# pic18f46k22_evb.net
KiCad netlist of a schematic drawn in EAGLE
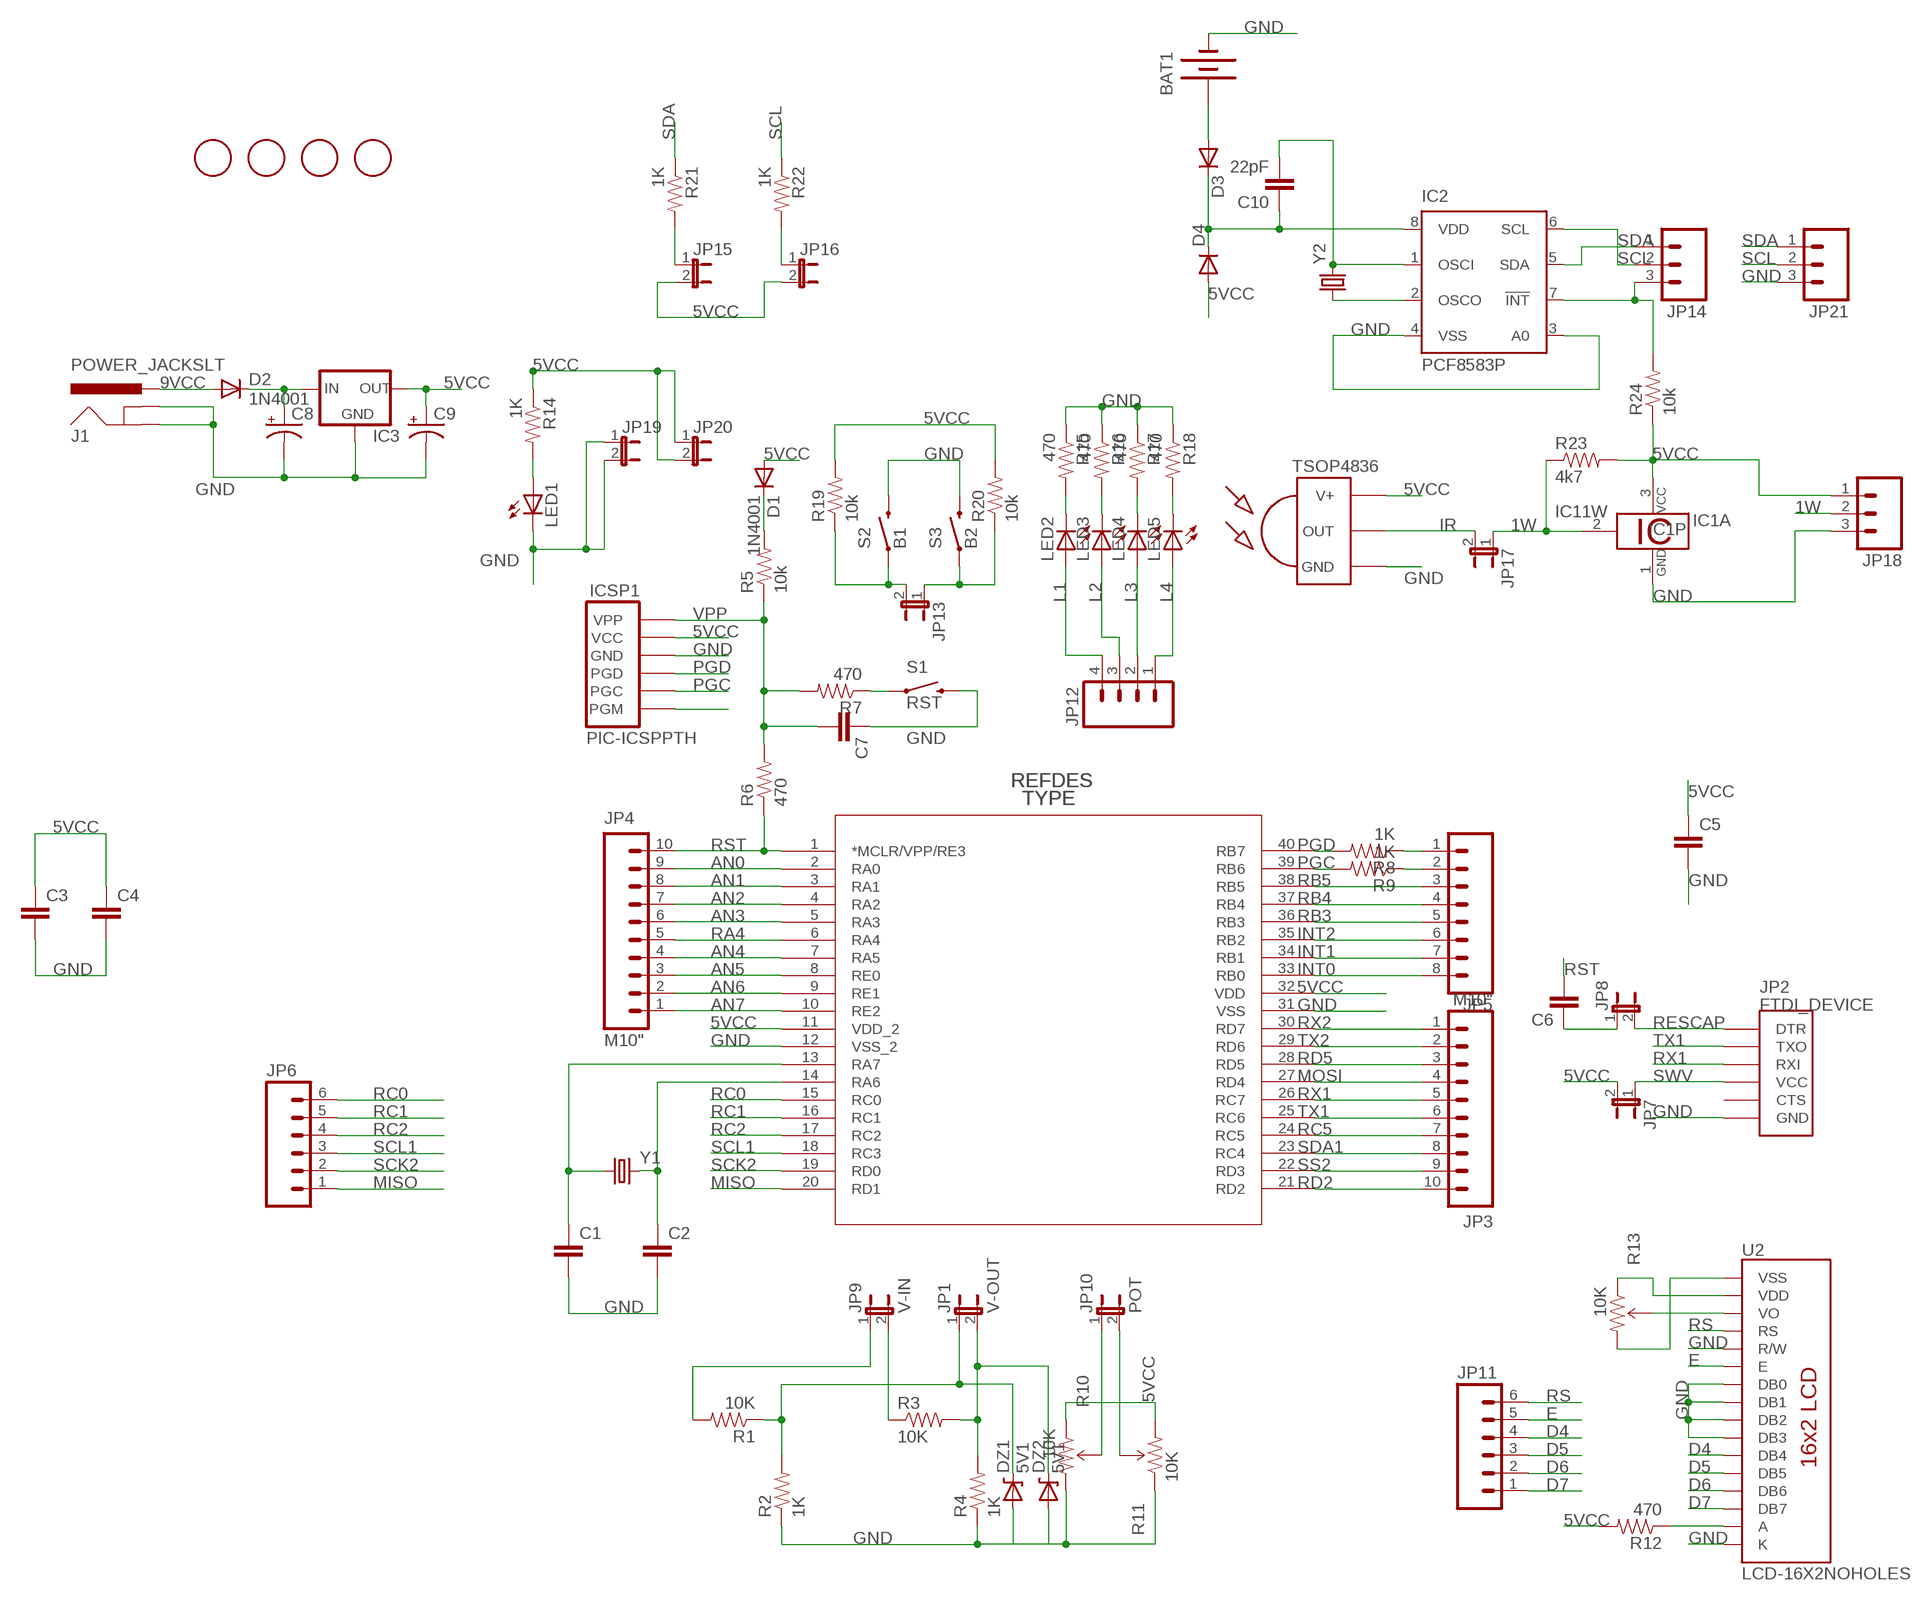
[diagram p0: schematic, sheet 1]

(export (version "E")
  (design (tool "Eeschema 10.0.6"))
  (components
    (comp (ref "BAT1")
      (value "BATTERY12MM")
      (footprint "eagle-import:BATTCON_12MM")
      (libsource (lib "eagle-import") (part "BATTERY12MM"))
    )
    (comp (ref "C1")
      (value "CAPPTH1")
      (footprint "eagle-import:CAP-PTH-5MM")
      (libsource (lib "eagle-import") (part "CAPPTH1"))
    )
    (comp (ref "C2")
      (value "CAPPTH1")
      (footprint "eagle-import:CAP-PTH-5MM")
      (libsource (lib "eagle-import") (part "CAPPTH1"))
    )
    (comp (ref "C3")
      (value "CAPPTH1")
      (footprint "eagle-import:CAP-PTH-5MM")
      (libsource (lib "eagle-import") (part "CAPPTH1"))
    )
    (comp (ref "C4")
      (value "CAPPTH1")
      (footprint "eagle-import:CAP-PTH-5MM")
      (libsource (lib "eagle-import") (part "CAPPTH1"))
    )
    (comp (ref "C5")
      (value "CAPPTH1")
      (footprint "eagle-import:CAP-PTH-5MM")
      (libsource (lib "eagle-import") (part "CAPPTH1"))
    )
    (comp (ref "C6")
      (value "CAPPTH1")
      (footprint "eagle-import:CAP-PTH-5MM")
      (libsource (lib "eagle-import") (part "CAPPTH1"))
    )
    (comp (ref "C7")
      (value "CAPPTH1")
      (footprint "eagle-import:CAP-PTH-5MM")
      (libsource (lib "eagle-import") (part "CAPPTH1"))
    )
    (comp (ref "C8")
      (value "CAP_POLPTH1")
      (footprint "eagle-import:CPOL-RADIAL-100UF-25V")
      (libsource (lib "eagle-import") (part "CAP_POLPTH1"))
    )
    (comp (ref "C9")
      (value "CAP_POLPTH2")
      (footprint "eagle-import:CPOL-RADIAL-10UF-25V")
      (libsource (lib "eagle-import") (part "CAP_POLPTH2"))
    )
    (comp (ref "C10")
      (value "22pF")
      (footprint "eagle-import:CAP-PTH-5MM")
      (libsource (lib "eagle-import") (part "CAPPTH1"))
    )
    (comp (ref "D1")
      (value "1N4001")
      (footprint "eagle-import:DIODE-1N4001")
      (libsource (lib "eagle-import") (part "DIODEPTH"))
    )
    (comp (ref "D2")
      (value "1N4001")
      (footprint "eagle-import:DIODE-1N4001")
      (libsource (lib "eagle-import") (part "DIODEPTH"))
    )
    (comp (ref "D3")
      (value "DIODE1N4148")
      (footprint "eagle-import:DIODE-1N4148")
      (libsource (lib "eagle-import") (part "DIODE1N4148"))
    )
    (comp (ref "D4")
      (value "DIODE1N4148")
      (footprint "eagle-import:DIODE-1N4148")
      (libsource (lib "eagle-import") (part "DIODE1N4148"))
    )
    (comp (ref "DZ1")
      (value "5V1")
      (footprint "eagle-import:DIODE-ZENER")
      (libsource (lib "eagle-import") (part "DIODE-ZENERPTH"))
    )
    (comp (ref "DZ2")
      (value "5V1")
      (footprint "eagle-import:DIODE-ZENER")
      (libsource (lib "eagle-import") (part "DIODE-ZENERPTH"))
    )
    (comp (ref "IC1")
      (value "DS18B20")
      (footprint "eagle-import:TO92-")
      (libsource (lib "eagle-import") (part "DS18B20"))
    )
    (comp (ref "IC2")
      (value "PCF8583P")
      (footprint "eagle-import:DIL08")
      (libsource (lib "eagle-import") (part "PCF8583P"))
    )
    (comp (ref "IC3")
      (value "V_REG_78XXSINK")
      (footprint "eagle-import:TO220-IGO")
      (libsource (lib "eagle-import") (part "V_REG_78XXSINK"))
    )
    (comp (ref "ICSP1")
      (value "PIC-ICSPPTH")
      (footprint "eagle-import:MOLEX-1X6")
      (libsource (lib "eagle-import") (part "PIC-ICSPPTH"))
    )
    (comp (ref "J1")
      (value "POWER_JACKSLT")
      (footprint "eagle-import:POWER_JACK_SLOT")
      (libsource (lib "eagle-import") (part "POWER_JACKSLT"))
    )
    (comp (ref "JP1")
      (value "V-OUT")
      (footprint "eagle-import:1X02")
      (libsource (lib "eagle-import") (part "JUMPER-2PTH"))
    )
    (comp (ref "JP2")
      (value "FTDI_DEVICE")
      (footprint "eagle-import:FTDI_DEVICE_SIDE")
      (libsource (lib "eagle-import") (part "FTDI_DEVICE"))
    )
    (comp (ref "JP3")
      (value "M10\"")
      (footprint "eagle-import:1X10")
      (libsource (lib "eagle-import") (part "M10{dblquote}"))
    )
    (comp (ref "JP4")
      (value "M10\"")
      (footprint "eagle-import:1X10")
      (libsource (lib "eagle-import") (part "M10{dblquote}"))
    )
    (comp (ref "JP5")
      (value "M081X08")
      (footprint "eagle-import:1X08")
      (libsource (lib "eagle-import") (part "M081X08"))
    )
    (comp (ref "JP6")
      (value "M06SIP")
      (footprint "eagle-import:1X06")
      (libsource (lib "eagle-import") (part "M06SIP"))
    )
    (comp (ref "JP7")
      (value "JUMPER-2PTH")
      (footprint "eagle-import:1X02")
      (libsource (lib "eagle-import") (part "JUMPER-2PTH"))
    )
    (comp (ref "JP8")
      (value "JUMPER-2PTH")
      (footprint "eagle-import:1X02")
      (libsource (lib "eagle-import") (part "JUMPER-2PTH"))
    )
    (comp (ref "JP9")
      (value "V-IN")
      (footprint "eagle-import:1X02")
      (libsource (lib "eagle-import") (part "JUMPER-2PTH"))
    )
    (comp (ref "JP10")
      (value "POT")
      (footprint "eagle-import:1X02")
      (libsource (lib "eagle-import") (part "JUMPER-2PTH"))
    )
    (comp (ref "JP11")
      (value "M06SIP")
      (footprint "eagle-import:1X06")
      (libsource (lib "eagle-import") (part "M06SIP"))
    )
    (comp (ref "JP12")
      (value "M04PTH")
      (footprint "eagle-import:1X04")
      (libsource (lib "eagle-import") (part "M04PTH"))
    )
    (comp (ref "JP13")
      (value "JUMPER-2PTH")
      (footprint "eagle-import:1X02")
      (libsource (lib "eagle-import") (part "JUMPER-2PTH"))
    )
    (comp (ref "JP14")
      (value "M03PTH")
      (footprint "eagle-import:1X03")
      (libsource (lib "eagle-import") (part "M03PTH"))
    )
    (comp (ref "JP15")
      (value "JUMPER-2PTH")
      (footprint "eagle-import:1X02")
      (libsource (lib "eagle-import") (part "JUMPER-2PTH"))
    )
    (comp (ref "JP16")
      (value "JUMPER-2PTH")
      (footprint "eagle-import:1X02")
      (libsource (lib "eagle-import") (part "JUMPER-2PTH"))
    )
    (comp (ref "JP17")
      (value "JUMPER-2PTH")
      (footprint "eagle-import:1X02")
      (libsource (lib "eagle-import") (part "JUMPER-2PTH"))
    )
    (comp (ref "JP18")
      (value "M03PTH")
      (footprint "eagle-import:1X03")
      (libsource (lib "eagle-import") (part "M03PTH"))
    )
    (comp (ref "JP19")
      (value "JUMPER-2PTH")
      (footprint "eagle-import:1X02")
      (libsource (lib "eagle-import") (part "JUMPER-2PTH"))
    )
    (comp (ref "JP20")
      (value "JUMPER-2PTH")
      (footprint "eagle-import:1X02")
      (libsource (lib "eagle-import") (part "JUMPER-2PTH"))
    )
    (comp (ref "JP21")
      (value "M03PTH")
      (footprint "eagle-import:1X03")
      (libsource (lib "eagle-import") (part "M03PTH"))
    )
    (comp (ref "LED1")
      (value "LED3MM")
      (footprint "eagle-import:LED3MM")
      (libsource (lib "eagle-import") (part "LED3MM"))
    )
    (comp (ref "LED2")
      (value "LED3MM")
      (footprint "eagle-import:LED3MM")
      (libsource (lib "eagle-import") (part "LED3MM"))
    )
    (comp (ref "LED3")
      (value "LED3MM")
      (footprint "eagle-import:LED3MM")
      (libsource (lib "eagle-import") (part "LED3MM"))
    )
    (comp (ref "LED4")
      (value "LED3MM")
      (footprint "eagle-import:LED3MM")
      (libsource (lib "eagle-import") (part "LED3MM"))
    )
    (comp (ref "LED5")
      (value "LED3MM")
      (footprint "eagle-import:LED3MM")
      (libsource (lib "eagle-import") (part "LED3MM"))
    )
    (comp (ref "R1")
      (value "10K")
      (footprint "eagle-import:AXIAL-0.3")
      (libsource (lib "eagle-import") (part "RESISTORAXIAL-0.3"))
    )
    (comp (ref "R2")
      (value "1K")
      (footprint "eagle-import:AXIAL-0.3")
      (libsource (lib "eagle-import") (part "SparkFun-Resistors_RESISTORAXIAL-0.3"))
    )
    (comp (ref "R3")
      (value "10K")
      (footprint "eagle-import:AXIAL-0.3")
      (libsource (lib "eagle-import") (part "RESISTORAXIAL-0.3"))
    )
    (comp (ref "R4")
      (value "1K")
      (footprint "eagle-import:AXIAL-0.3")
      (libsource (lib "eagle-import") (part "RESISTORAXIAL-0.3"))
    )
    (comp (ref "R5")
      (value "10k")
      (footprint "eagle-import:AXIAL-0.3")
      (libsource (lib "eagle-import") (part "SparkFun-Resistors_RESISTORAXIAL-0.3"))
    )
    (comp (ref "R6")
      (value "470")
      (footprint "eagle-import:AXIAL-0.3")
      (libsource (lib "eagle-import") (part "RESISTORAXIAL-0.3"))
    )
    (comp (ref "R7")
      (value "470")
      (footprint "eagle-import:AXIAL-0.3")
      (libsource (lib "eagle-import") (part "RESISTORAXIAL-0.3"))
    )
    (comp (ref "R8")
      (value "1K")
      (footprint "eagle-import:AXIAL-0.3")
      (libsource (lib "eagle-import") (part "RESISTORAXIAL-0.3"))
    )
    (comp (ref "R9")
      (value "1K")
      (footprint "eagle-import:AXIAL-0.3")
      (libsource (lib "eagle-import") (part "RESISTORAXIAL-0.3"))
    )
    (comp (ref "R10")
      (value "10K")
      (footprint "eagle-import:TRIM_POT_PTH")
      (libsource (lib "eagle-import") (part "TRIMPOTPTH"))
    )
    (comp (ref "R11")
      (value "10K")
      (footprint "eagle-import:TRIM_POT_PTH")
      (libsource (lib "eagle-import") (part "TRIMPOTPTH"))
    )
    (comp (ref "R12")
      (value "470")
      (footprint "eagle-import:AXIAL-0.3")
      (libsource (lib "eagle-import") (part "RESISTORAXIAL-0.3"))
    )
    (comp (ref "R13")
      (value "10K")
      (footprint "eagle-import:TRIM_POT_PTH")
      (libsource (lib "eagle-import") (part "TRIMPOTPTH"))
    )
    (comp (ref "R14")
      (value "1K")
      (footprint "eagle-import:AXIAL-0.3")
      (libsource (lib "eagle-import") (part "RESISTORAXIAL-0.3"))
    )
    (comp (ref "R15")
      (value "470")
      (footprint "eagle-import:AXIAL-0.3")
      (libsource (lib "eagle-import") (part "RESISTORAXIAL-0.3"))
    )
    (comp (ref "R16")
      (value "470")
      (footprint "eagle-import:AXIAL-0.3")
      (libsource (lib "eagle-import") (part "RESISTORAXIAL-0.3"))
    )
    (comp (ref "R17")
      (value "470")
      (footprint "eagle-import:AXIAL-0.3")
      (libsource (lib "eagle-import") (part "RESISTORAXIAL-0.3"))
    )
    (comp (ref "R18")
      (value "470")
      (footprint "eagle-import:AXIAL-0.3")
      (libsource (lib "eagle-import") (part "RESISTORAXIAL-0.3"))
    )
    (comp (ref "R19")
      (value "10k")
      (footprint "eagle-import:AXIAL-0.3")
      (libsource (lib "eagle-import") (part "SparkFun-Resistors_RESISTORAXIAL-0.3"))
    )
    (comp (ref "R20")
      (value "10k")
      (footprint "eagle-import:AXIAL-0.3")
      (libsource (lib "eagle-import") (part "SparkFun-Resistors_RESISTORAXIAL-0.3"))
    )
    (comp (ref "R21")
      (value "1K")
      (footprint "eagle-import:AXIAL-0.3")
      (libsource (lib "eagle-import") (part "RESISTORAXIAL-0.3"))
    )
    (comp (ref "R22")
      (value "1K")
      (footprint "eagle-import:AXIAL-0.3")
      (libsource (lib "eagle-import") (part "RESISTORAXIAL-0.3"))
    )
    (comp (ref "R23")
      (value "4k7")
      (footprint "eagle-import:AXIAL-0.3")
      (libsource (lib "eagle-import") (part "RESISTORAXIAL-0.3"))
    )
    (comp (ref "R24")
      (value "10k")
      (footprint "eagle-import:AXIAL-0.3")
      (libsource (lib "eagle-import") (part "SparkFun-Resistors_RESISTORAXIAL-0.3"))
    )
    (comp (ref "S1")
      (value "RST")
      (footprint "eagle-import:TACTILE-PTH")
      (libsource (lib "eagle-import") (part "SWITCH-MOMENTARY-2PTH"))
    )
    (comp (ref "S2")
      (value "B1")
      (footprint "eagle-import:TACTILE-PTH")
      (libsource (lib "eagle-import") (part "SWITCH-MOMENTARY-2PTH"))
    )
    (comp (ref "S3")
      (value "B2")
      (footprint "eagle-import:TACTILE-PTH")
      (libsource (lib "eagle-import") (part "SWITCH-MOMENTARY-2PTH"))
    )
    (comp (ref "U$1")
      (value "MOUNTINGHOLE3.0THIN")
      (footprint "eagle-import:MOUNTINGHOLE_3.0_PLATEDTHIN")
      (libsource (lib "eagle-import") (part "MOUNTINGHOLE3.0THIN"))
    )
    (comp (ref "U$2")
      (value "MOUNTINGHOLE3.0THIN")
      (footprint "eagle-import:MOUNTINGHOLE_3.0_PLATEDTHIN")
      (libsource (lib "eagle-import") (part "MOUNTINGHOLE3.0THIN"))
    )
    (comp (ref "U$3")
      (value "MOUNTINGHOLE3.0THIN")
      (footprint "eagle-import:MOUNTINGHOLE_3.0_PLATEDTHIN")
      (libsource (lib "eagle-import") (part "MOUNTINGHOLE3.0THIN"))
    )
    (comp (ref "U$4")
      (value "MOUNTINGHOLE3.0THIN")
      (footprint "eagle-import:MOUNTINGHOLE_3.0_PLATEDTHIN")
      (libsource (lib "eagle-import") (part "MOUNTINGHOLE3.0THIN"))
    )
    (comp (ref "U$5")
      (value "TSOP4836")
      (footprint "eagle-import:TSOP18XX")
      (libsource (lib "eagle-import") (part "TSOP4836"))
    )
    (comp (ref "U1")
      (value "PIC18F46K22")
      (footprint "eagle-import:MICROCHIP_PDIP40_600MC")
      (libsource (lib "eagle-import") (part "MICROCHIP_PIC18F46K22-X_P"))
    )
    (comp (ref "U2")
      (value "LCD-16X2NOHOLES")
      (footprint "eagle-import:LCD-16X2_NOHOLES")
      (libsource (lib "eagle-import") (part "LCD-16X2NOHOLES"))
    )
    (comp (ref "Y1")
      (value "CRYSTALHC49UV")
      (footprint "eagle-import:HC49U-V")
      (libsource (lib "eagle-import") (part "CRYSTALHC49UV"))
    )
    (comp (ref "Y2")
      (value "CRYSTALTC38H")
      (footprint "eagle-import:TC38H")
      (libsource (lib "eagle-import") (part "CRYSTALTC38H"))
    )
  )
  (nets
    (net (code "1") (name "/1W") (class "Default")
      (node (ref "IC1") (pin "2") (pinfunction "1W_2") (pintype "power_in"))
      (node (ref "JP17") (pin "1") (pinfunction "1_1") (pintype "passive"))
      (node (ref "JP18") (pin "2") (pinfunction "2_2") (pintype "passive"))
      (node (ref "R23") (pin "P$1") (pinfunction "1_P$1") (pintype "passive"))
    )
    (net (code "2") (name "/5VCC") (class "Default")
      (node (ref "C3") (pin "1") (pinfunction "1_1") (pintype "passive"))
      (node (ref "C4") (pin "1") (pinfunction "1_1") (pintype "passive"))
      (node (ref "C5") (pin "1") (pinfunction "1_1") (pintype "passive"))
      (node (ref "C9") (pin "1") (pinfunction "+_1") (pintype "passive"))
      (node (ref "D1") (pin "A") (pinfunction "A_A") (pintype "passive"))
      (node (ref "D4") (pin "A") (pinfunction "A_A") (pintype "passive"))
      (node (ref "IC1") (pin "3") (pinfunction "VDD_3") (pintype "power_in"))
      (node (ref "IC3") (pin "OUT") (pinfunction "OUT_OUT") (pintype "output"))
      (node (ref "ICSP1") (pin "5") (pinfunction "VCC_5") (pintype "bidirectional"))
      (node (ref "JP15") (pin "2") (pinfunction "2_2") (pintype "passive"))
      (node (ref "JP16") (pin "2") (pinfunction "2_2") (pintype "passive"))
      (node (ref "JP18") (pin "1") (pinfunction "1_1") (pintype "passive"))
      (node (ref "JP20") (pin "1") (pinfunction "1_1") (pintype "passive"))
      (node (ref "JP20") (pin "2") (pinfunction "2_2") (pintype "passive"))
      (node (ref "JP7") (pin "2") (pinfunction "2_2") (pintype "passive"))
      (node (ref "R10") (pin "1") (pinfunction "CCW_1") (pintype "passive"))
      (node (ref "R11") (pin "3") (pinfunction "CW_3") (pintype "passive"))
      (node (ref "R12") (pin "P$2") (pinfunction "2_P$2") (pintype "passive"))
      (node (ref "R13") (pin "1") (pinfunction "CCW_1") (pintype "passive"))
      (node (ref "R14") (pin "P$1") (pinfunction "1_P$1") (pintype "passive"))
      (node (ref "R19") (pin "P$2") (pinfunction "2_P$2") (pintype "passive"))
      (node (ref "R20") (pin "P$2") (pinfunction "2_P$2") (pintype "passive"))
      (node (ref "R23") (pin "P$2") (pinfunction "2_P$2") (pintype "passive"))
      (node (ref "R24") (pin "P$1") (pinfunction "1_P$1") (pintype "passive"))
      (node (ref "U$5") (pin "VCC") (pinfunction "V+_VCC") (pintype "bidirectional"))
      (node (ref "U1") (pin "11") (pinfunction "VDD_2_11") (pintype "passive"))
      (node (ref "U1") (pin "32") (pinfunction "VDD_32") (pintype "passive"))
      (node (ref "U2") (pin "2") (pinfunction "VDD_2") (pintype "power_in"))
    )
    (net (code "3") (name "/9VCC") (class "Default")
      (node (ref "D2") (pin "A") (pinfunction "A_A") (pintype "passive"))
      (node (ref "J1") (pin "PWR") (pinfunction "PWR_PWR") (pintype "bidirectional"))
    )
    (net (code "4") (name "/AN0") (class "Default")
      (node (ref "JP4") (pin "9") (pinfunction "9_9") (pintype "passive"))
      (node (ref "U1") (pin "2") (pinfunction "RA0_2") (pintype "passive"))
    )
    (net (code "5") (name "/AN1") (class "Default")
      (node (ref "JP4") (pin "8") (pinfunction "8_8") (pintype "passive"))
      (node (ref "U1") (pin "3") (pinfunction "RA1_3") (pintype "passive"))
    )
    (net (code "6") (name "/AN2") (class "Default")
      (node (ref "JP4") (pin "7") (pinfunction "7_7") (pintype "passive"))
      (node (ref "U1") (pin "4") (pinfunction "RA2_4") (pintype "passive"))
    )
    (net (code "7") (name "/AN3") (class "Default")
      (node (ref "JP4") (pin "6") (pinfunction "6_6") (pintype "passive"))
      (node (ref "U1") (pin "5") (pinfunction "RA3_5") (pintype "passive"))
    )
    (net (code "8") (name "/AN4") (class "Default")
      (node (ref "JP4") (pin "4") (pinfunction "4_4") (pintype "passive"))
      (node (ref "U1") (pin "7") (pinfunction "RA5_7") (pintype "passive"))
    )
    (net (code "9") (name "/AN5") (class "Default")
      (node (ref "JP4") (pin "3") (pinfunction "3_3") (pintype "passive"))
      (node (ref "U1") (pin "8") (pinfunction "RE0_8") (pintype "passive"))
    )
    (net (code "10") (name "/AN6") (class "Default")
      (node (ref "JP4") (pin "2") (pinfunction "2_2") (pintype "passive"))
      (node (ref "U1") (pin "9") (pinfunction "RE1_9") (pintype "passive"))
    )
    (net (code "11") (name "/AN7") (class "Default")
      (node (ref "JP4") (pin "1") (pinfunction "1_1") (pintype "passive"))
      (node (ref "U1") (pin "10") (pinfunction "RE2_10") (pintype "passive"))
    )
    (net (code "12") (name "/D4") (class "Default")
      (node (ref "JP11") (pin "4") (pinfunction "4_4") (pintype "passive"))
      (node (ref "U2") (pin "11") (pinfunction "DB4_11") (pintype "bidirectional"))
    )
    (net (code "13") (name "/D5") (class "Default")
      (node (ref "JP11") (pin "3") (pinfunction "3_3") (pintype "passive"))
      (node (ref "U2") (pin "12") (pinfunction "DB5_12") (pintype "bidirectional"))
    )
    (net (code "14") (name "/D6") (class "Default")
      (node (ref "JP11") (pin "2") (pinfunction "2_2") (pintype "passive"))
      (node (ref "U2") (pin "13") (pinfunction "DB6_13") (pintype "bidirectional"))
    )
    (net (code "15") (name "/D7") (class "Default")
      (node (ref "JP11") (pin "1") (pinfunction "1_1") (pintype "passive"))
      (node (ref "U2") (pin "14") (pinfunction "DB7_14") (pintype "bidirectional"))
    )
    (net (code "16") (name "/E") (class "Default")
      (node (ref "JP11") (pin "5") (pinfunction "5_5") (pintype "passive"))
      (node (ref "U2") (pin "6") (pinfunction "E_6") (pintype "input"))
    )
    (net (code "17") (name "/GND") (class "Default")
      (node (ref "BAT1") (pin "GND") (pinfunction "-_GND") (pintype "power_in"))
      (node (ref "C1") (pin "2") (pinfunction "2_2") (pintype "passive"))
      (node (ref "C2") (pin "2") (pinfunction "2_2") (pintype "passive"))
      (node (ref "C3") (pin "2") (pinfunction "2_2") (pintype "passive"))
      (node (ref "C4") (pin "2") (pinfunction "2_2") (pintype "passive"))
      (node (ref "C5") (pin "2") (pinfunction "2_2") (pintype "passive"))
      (node (ref "C7") (pin "1") (pinfunction "1_1") (pintype "passive"))
      (node (ref "C8") (pin "2") (pinfunction "-_2") (pintype "passive"))
      (node (ref "C9") (pin "2") (pinfunction "-_2") (pintype "passive"))
      (node (ref "DZ1") (pin "P$2") (pinfunction "A_P$2") (pintype "passive"))
      (node (ref "DZ2") (pin "P$2") (pinfunction "A_P$2") (pintype "passive"))
      (node (ref "IC1") (pin "1") (pinfunction "GND_1") (pintype "power_in"))
      (node (ref "IC2") (pin "3") (pinfunction "A0_3") (pintype "input"))
      (node (ref "IC2") (pin "4") (pinfunction "VSS_4") (pintype "power_in"))
      (node (ref "IC3") (pin "GND") (pinfunction "GND_GND") (pintype "input"))
      (node (ref "ICSP1") (pin "4") (pinfunction "GND_4") (pintype "bidirectional"))
      (node (ref "J1") (pin "GND@1") (pinfunction "GNDBREAK_GND@1") (pintype "bidirectional"))
      (node (ref "J1") (pin "GND@2") (pinfunction "GND_GND@2") (pintype "bidirectional"))
      (node (ref "JP18") (pin "3") (pinfunction "3_3") (pintype "passive"))
      (node (ref "JP19") (pin "1") (pinfunction "1_1") (pintype "passive"))
      (node (ref "JP19") (pin "2") (pinfunction "2_2") (pintype "passive"))
      (node (ref "JP2") (pin "P$6") (pinfunction "GND_P$6") (pintype "bidirectional"))
      (node (ref "JP21") (pin "3") (pinfunction "3_3") (pintype "passive"))
      (node (ref "LED1") (pin "K") (pinfunction "C_K") (pintype "passive"))
      (node (ref "R10") (pin "3") (pinfunction "CW_3") (pintype "passive"))
      (node (ref "R11") (pin "1") (pinfunction "CCW_1") (pintype "passive"))
      (node (ref "R13") (pin "3") (pinfunction "CW_3") (pintype "passive"))
      (node (ref "R15") (pin "P$1") (pinfunction "1_P$1") (pintype "passive"))
      (node (ref "R16") (pin "P$1") (pinfunction "1_P$1") (pintype "passive"))
      (node (ref "R17") (pin "P$1") (pinfunction "1_P$1") (pintype "passive"))
      (node (ref "R18") (pin "P$1") (pinfunction "1_P$1") (pintype "passive"))
      (node (ref "R2") (pin "P$1") (pinfunction "1_P$1") (pintype "passive"))
      (node (ref "R4") (pin "P$1") (pinfunction "1_P$1") (pintype "passive"))
      (node (ref "S1") (pin "3") (pinfunction "2_3") (pintype "passive"))
      (node (ref "S2") (pin "3") (pinfunction "2_3") (pintype "passive"))
      (node (ref "S3") (pin "3") (pinfunction "2_3") (pintype "passive"))
      (node (ref "U$5") (pin "GND") (pinfunction "GND_GND") (pintype "bidirectional"))
      (node (ref "U1") (pin "12") (pinfunction "VSS_2_12") (pintype "passive"))
      (node (ref "U1") (pin "31") (pinfunction "VSS_31") (pintype "passive"))
      (node (ref "U2") (pin "1") (pinfunction "VSS_1") (pintype "power_in"))
      (node (ref "U2") (pin "10") (pinfunction "DB3_10") (pintype "bidirectional"))
      (node (ref "U2") (pin "16") (pinfunction "K_16") (pintype "power_in"))
      (node (ref "U2") (pin "5") (pinfunction "R/W_5") (pintype "input"))
      (node (ref "U2") (pin "7") (pinfunction "DB0_7") (pintype "bidirectional"))
      (node (ref "U2") (pin "8") (pinfunction "DB1_8") (pintype "bidirectional"))
      (node (ref "U2") (pin "9") (pinfunction "DB2_9") (pintype "bidirectional"))
    )
    (net (code "18") (name "/INT0") (class "Default")
      (node (ref "JP5") (pin "8") (pinfunction "8_8") (pintype "passive"))
      (node (ref "U1") (pin "33") (pinfunction "RB0_33") (pintype "passive"))
    )
    (net (code "19") (name "/INT1") (class "Default")
      (node (ref "JP5") (pin "7") (pinfunction "7_7") (pintype "passive"))
      (node (ref "U1") (pin "34") (pinfunction "RB1_34") (pintype "passive"))
    )
    (net (code "20") (name "/INT2") (class "Default")
      (node (ref "JP5") (pin "6") (pinfunction "6_6") (pintype "passive"))
      (node (ref "U1") (pin "35") (pinfunction "RB2_35") (pintype "passive"))
    )
    (net (code "21") (name "/IR") (class "Default")
      (node (ref "JP17") (pin "2") (pinfunction "2_2") (pintype "passive"))
      (node (ref "U$5") (pin "OUT") (pinfunction "OUT_OUT") (pintype "bidirectional"))
    )
    (net (code "22") (name "/L1") (class "Default")
      (node (ref "JP12") (pin "4") (pinfunction "4_4") (pintype "passive"))
      (node (ref "LED2") (pin "A") (pinfunction "A_A") (pintype "passive"))
    )
    (net (code "23") (name "/L2") (class "Default")
      (node (ref "JP12") (pin "3") (pinfunction "3_3") (pintype "passive"))
      (node (ref "LED3") (pin "A") (pinfunction "A_A") (pintype "passive"))
    )
    (net (code "24") (name "/L3") (class "Default")
      (node (ref "JP12") (pin "2") (pinfunction "2_2") (pintype "passive"))
      (node (ref "LED4") (pin "A") (pinfunction "A_A") (pintype "passive"))
    )
    (net (code "25") (name "/L4") (class "Default")
      (node (ref "JP12") (pin "1") (pinfunction "1_1") (pintype "passive"))
      (node (ref "LED5") (pin "A") (pinfunction "A_A") (pintype "passive"))
    )
    (net (code "26") (name "/MISO") (class "Default")
      (node (ref "JP6") (pin "1") (pinfunction "1_1") (pintype "passive"))
      (node (ref "U1") (pin "20") (pinfunction "RD1_20") (pintype "passive"))
    )
    (net (code "27") (name "/MOSI") (class "Default")
      (node (ref "JP3") (pin "4") (pinfunction "4_4") (pintype "passive"))
      (node (ref "U1") (pin "27") (pinfunction "RD4_27") (pintype "passive"))
    )
    (net (code "28") (name "/PGC") (class "Default")
      (node (ref "ICSP1") (pin "2") (pinfunction "PGC_2") (pintype "bidirectional"))
      (node (ref "R9") (pin "P$2") (pinfunction "2_P$2") (pintype "passive"))
      (node (ref "U1") (pin "39") (pinfunction "RB6_39") (pintype "passive"))
    )
    (net (code "29") (name "/PGD") (class "Default")
      (node (ref "ICSP1") (pin "3") (pinfunction "PGD_3") (pintype "bidirectional"))
      (node (ref "R8") (pin "P$2") (pinfunction "2_P$2") (pintype "passive"))
      (node (ref "U1") (pin "40") (pinfunction "RB7_40") (pintype "passive"))
    )
    (net (code "30") (name "/RA4") (class "Default")
      (node (ref "JP4") (pin "5") (pinfunction "5_5") (pintype "passive"))
      (node (ref "U1") (pin "6") (pinfunction "RA4_6") (pintype "passive"))
    )
    (net (code "31") (name "/RB3") (class "Default")
      (node (ref "JP5") (pin "5") (pinfunction "5_5") (pintype "passive"))
      (node (ref "U1") (pin "36") (pinfunction "RB3_36") (pintype "passive"))
    )
    (net (code "32") (name "/RB4") (class "Default")
      (node (ref "JP5") (pin "4") (pinfunction "4_4") (pintype "passive"))
      (node (ref "U1") (pin "37") (pinfunction "RB4_37") (pintype "passive"))
    )
    (net (code "33") (name "/RB5") (class "Default")
      (node (ref "JP5") (pin "3") (pinfunction "3_3") (pintype "passive"))
      (node (ref "U1") (pin "38") (pinfunction "RB5_38") (pintype "passive"))
    )
    (net (code "34") (name "/RC0") (class "Default")
      (node (ref "JP6") (pin "6") (pinfunction "6_6") (pintype "passive"))
      (node (ref "U1") (pin "15") (pinfunction "RC0_15") (pintype "passive"))
    )
    (net (code "35") (name "/RC1") (class "Default")
      (node (ref "JP6") (pin "5") (pinfunction "5_5") (pintype "passive"))
      (node (ref "U1") (pin "16") (pinfunction "RC1_16") (pintype "passive"))
    )
    (net (code "36") (name "/RC2") (class "Default")
      (node (ref "JP6") (pin "4") (pinfunction "4_4") (pintype "passive"))
      (node (ref "U1") (pin "17") (pinfunction "RC2_17") (pintype "passive"))
    )
    (net (code "37") (name "/RC5") (class "Default")
      (node (ref "JP3") (pin "7") (pinfunction "7_7") (pintype "passive"))
      (node (ref "U1") (pin "24") (pinfunction "RC5_24") (pintype "passive"))
    )
    (net (code "38") (name "/RD2") (class "Default")
      (node (ref "JP3") (pin "10") (pinfunction "10_10") (pintype "passive"))
      (node (ref "U1") (pin "21") (pinfunction "RD2_21") (pintype "passive"))
    )
    (net (code "39") (name "/RD5") (class "Default")
      (node (ref "JP3") (pin "3") (pinfunction "3_3") (pintype "passive"))
      (node (ref "U1") (pin "28") (pinfunction "RD5_28") (pintype "passive"))
    )
    (net (code "40") (name "/RESCAP") (class "Default")
      (node (ref "JP2") (pin "P$1") (pinfunction "DTR_P$1") (pintype "bidirectional"))
      (node (ref "JP8") (pin "2") (pinfunction "2_2") (pintype "passive"))
    )
    (net (code "41") (name "/RS") (class "Default")
      (node (ref "JP11") (pin "6") (pinfunction "6_6") (pintype "passive"))
      (node (ref "U2") (pin "4") (pinfunction "RS_4") (pintype "input"))
    )
    (net (code "42") (name "/RST") (class "Default")
      (node (ref "C6") (pin "2") (pinfunction "2_2") (pintype "passive"))
      (node (ref "JP4") (pin "10") (pinfunction "10_10") (pintype "passive"))
      (node (ref "R6") (pin "P$1") (pinfunction "1_P$1") (pintype "passive"))
      (node (ref "U1") (pin "1") (pinfunction "*MCLR/VPP/RE3_1") (pintype "passive"))
    )
    (net (code "43") (name "/RX1") (class "Default")
      (node (ref "JP2") (pin "P$3") (pinfunction "RXI_P$3") (pintype "bidirectional"))
      (node (ref "JP3") (pin "5") (pinfunction "5_5") (pintype "passive"))
      (node (ref "U1") (pin "26") (pinfunction "RC7_26") (pintype "passive"))
    )
    (net (code "44") (name "/RX2") (class "Default")
      (node (ref "JP3") (pin "1") (pinfunction "1_1") (pintype "passive"))
      (node (ref "U1") (pin "30") (pinfunction "RD7_30") (pintype "passive"))
    )
    (net (code "45") (name "/SCK2") (class "Default")
      (node (ref "JP6") (pin "2") (pinfunction "2_2") (pintype "passive"))
      (node (ref "U1") (pin "19") (pinfunction "RD0_19") (pintype "passive"))
    )
    (net (code "46") (name "/SCL") (class "Default")
      (node (ref "IC2") (pin "6") (pinfunction "SCL_6") (pintype "input"))
      (node (ref "JP14") (pin "2") (pinfunction "2_2") (pintype "passive"))
      (node (ref "JP21") (pin "2") (pinfunction "2_2") (pintype "passive"))
      (node (ref "R22") (pin "P$1") (pinfunction "1_P$1") (pintype "passive"))
    )
    (net (code "47") (name "/SCL1") (class "Default")
      (node (ref "JP6") (pin "3") (pinfunction "3_3") (pintype "passive"))
      (node (ref "U1") (pin "18") (pinfunction "RC3_18") (pintype "passive"))
    )
    (net (code "48") (name "/SDA") (class "Default")
      (node (ref "IC2") (pin "5") (pinfunction "SDA_5") (pintype "bidirectional"))
      (node (ref "JP14") (pin "1") (pinfunction "1_1") (pintype "passive"))
      (node (ref "JP21") (pin "1") (pinfunction "1_1") (pintype "passive"))
      (node (ref "R21") (pin "P$1") (pinfunction "1_P$1") (pintype "passive"))
    )
    (net (code "49") (name "/SDA1") (class "Default")
      (node (ref "JP3") (pin "8") (pinfunction "8_8") (pintype "passive"))
      (node (ref "U1") (pin "23") (pinfunction "RC4_23") (pintype "passive"))
    )
    (net (code "50") (name "/SS2") (class "Default")
      (node (ref "JP3") (pin "9") (pinfunction "9_9") (pintype "passive"))
      (node (ref "U1") (pin "22") (pinfunction "RD3_22") (pintype "passive"))
    )
    (net (code "51") (name "/SWV") (class "Default")
      (node (ref "JP2") (pin "P$4") (pinfunction "VCC_P$4") (pintype "bidirectional"))
      (node (ref "JP7") (pin "1") (pinfunction "1_1") (pintype "passive"))
    )
    (net (code "52") (name "/TX1") (class "Default")
      (node (ref "JP2") (pin "P$2") (pinfunction "TXO_P$2") (pintype "bidirectional"))
      (node (ref "JP3") (pin "6") (pinfunction "6_6") (pintype "passive"))
      (node (ref "U1") (pin "25") (pinfunction "RC6_25") (pintype "passive"))
    )
    (net (code "53") (name "/TX2") (class "Default")
      (node (ref "JP3") (pin "2") (pinfunction "2_2") (pintype "passive"))
      (node (ref "U1") (pin "29") (pinfunction "RD6_29") (pintype "passive"))
    )
    (net (code "54") (name "/VPP") (class "Default")
      (node (ref "C7") (pin "2") (pinfunction "2_2") (pintype "passive"))
      (node (ref "ICSP1") (pin "6") (pinfunction "VPP_6") (pintype "bidirectional"))
      (node (ref "R5") (pin "P$1") (pinfunction "1_P$1") (pintype "passive"))
      (node (ref "R6") (pin "P$2") (pinfunction "2_P$2") (pintype "passive"))
      (node (ref "R7") (pin "P$2") (pinfunction "2_P$2") (pintype "passive"))
    )
    (net (code "55") (name "Net-(BAT1-+)") (class "Default")
      (node (ref "BAT1") (pin "PWR@1") (pinfunction "+_PWR@1") (pintype "power_in"))
      (node (ref "D3") (pin "A") (pinfunction "A_A") (pintype "passive"))
    )
    (net (code "56") (name "Net-(C6-Pad1)") (class "Default")
      (node (ref "C6") (pin "1") (pinfunction "1_1") (pintype "passive"))
      (node (ref "JP8") (pin "1") (pinfunction "1_1") (pintype "passive"))
    )
    (net (code "57") (name "Net-(C8-+)") (class "Default")
      (node (ref "C8") (pin "1") (pinfunction "+_1") (pintype "passive"))
      (node (ref "D2") (pin "C") (pinfunction "C_C") (pintype "passive"))
      (node (ref "IC3") (pin "IN") (pinfunction "IN_IN") (pintype "input"))
    )
    (net (code "58") (name "Net-(DZ1-C)") (class "Default")
      (node (ref "DZ1") (pin "P$1") (pinfunction "C_P$1") (pintype "passive"))
      (node (ref "JP1") (pin "1") (pinfunction "1_1") (pintype "passive"))
      (node (ref "R1") (pin "P$1") (pinfunction "1_P$1") (pintype "passive"))
      (node (ref "R2") (pin "P$2") (pinfunction "2_P$2") (pintype "passive"))
    )
    (net (code "59") (name "Net-(DZ2-C)") (class "Default")
      (node (ref "DZ2") (pin "P$1") (pinfunction "C_P$1") (pintype "passive"))
      (node (ref "JP1") (pin "2") (pinfunction "2_2") (pintype "passive"))
      (node (ref "R3") (pin "P$2") (pinfunction "2_P$2") (pintype "passive"))
      (node (ref "R4") (pin "P$2") (pinfunction "2_P$2") (pintype "passive"))
    )
    (net (code "60") (name "Net-(IC2-OSCI)") (class "Default")
      (node (ref "C10") (pin "2") (pinfunction "2_2") (pintype "passive"))
      (node (ref "IC2") (pin "1") (pinfunction "OSCI_1") (pintype "input"))
      (node (ref "Y2") (pin "2") (pinfunction "2_2") (pintype "passive"))
    )
    (net (code "61") (name "Net-(IC2-OSCO)") (class "Default")
      (node (ref "IC2") (pin "2") (pinfunction "OSCO_2") (pintype "output"))
      (node (ref "Y2") (pin "1") (pinfunction "1_1") (pintype "passive"))
    )
    (net (code "62") (name "Net-(IC2-VDD)") (class "Default")
      (node (ref "C10") (pin "1") (pinfunction "1_1") (pintype "passive"))
      (node (ref "D3") (pin "C") (pinfunction "C_C") (pintype "passive"))
      (node (ref "D4") (pin "C") (pinfunction "C_C") (pintype "passive"))
      (node (ref "IC2") (pin "8") (pinfunction "VDD_8") (pintype "power_in"))
    )
    (net (code "63") (name "Net-(IC2-~{INT})") (class "Default")
      (node (ref "IC2") (pin "7") (pinfunction "~{INT}_7") (pintype "open_collector"))
      (node (ref "JP14") (pin "3") (pinfunction "3_3") (pintype "passive"))
      (node (ref "R24") (pin "P$2") (pinfunction "2_P$2") (pintype "passive"))
    )
    (net (code "64") (name "Net-(LED2-C)") (class "Default")
      (node (ref "LED2") (pin "K") (pinfunction "C_K") (pintype "passive"))
      (node (ref "R15") (pin "P$2") (pinfunction "2_P$2") (pintype "passive"))
    )
    (net (code "65") (name "Net-(LED3-C)") (class "Default")
      (node (ref "LED3") (pin "K") (pinfunction "C_K") (pintype "passive"))
      (node (ref "R16") (pin "P$2") (pinfunction "2_P$2") (pintype "passive"))
    )
    (net (code "66") (name "Net-(LED4-C)") (class "Default")
      (node (ref "LED4") (pin "K") (pinfunction "C_K") (pintype "passive"))
      (node (ref "R17") (pin "P$2") (pinfunction "2_P$2") (pintype "passive"))
    )
    (net (code "67") (name "Net-(LED5-C)") (class "Default")
      (node (ref "LED5") (pin "K") (pinfunction "C_K") (pintype "passive"))
      (node (ref "R18") (pin "P$2") (pinfunction "2_P$2") (pintype "passive"))
    )
    (net (code "68") (name "Net-(R1-2)") (class "Default")
      (node (ref "JP9") (pin "1") (pinfunction "1_1") (pintype "passive"))
      (node (ref "R1") (pin "P$2") (pinfunction "2_P$2") (pintype "passive"))
    )
    (net (code "69") (name "Net-(R3-1)") (class "Default")
      (node (ref "JP9") (pin "2") (pinfunction "2_2") (pintype "passive"))
      (node (ref "R3") (pin "P$1") (pinfunction "1_P$1") (pintype "passive"))
    )
    (net (code "70") (name "Net-(R5-2)") (class "Default")
      (node (ref "D1") (pin "C") (pinfunction "C_C") (pintype "passive"))
      (node (ref "R5") (pin "P$2") (pinfunction "2_P$2") (pintype "passive"))
    )
    (net (code "71") (name "Net-(R7-1)") (class "Default")
      (node (ref "R7") (pin "P$1") (pinfunction "1_P$1") (pintype "passive"))
      (node (ref "S1") (pin "1") (pinfunction "1_1") (pintype "passive"))
    )
    (net (code "72") (name "Net-(R8-1)") (class "Default")
      (node (ref "JP5") (pin "1") (pinfunction "1_1") (pintype "passive"))
      (node (ref "R8") (pin "P$1") (pinfunction "1_P$1") (pintype "passive"))
    )
    (net (code "73") (name "Net-(R9-1)") (class "Default")
      (node (ref "JP5") (pin "2") (pinfunction "2_2") (pintype "passive"))
      (node (ref "R9") (pin "P$1") (pinfunction "1_P$1") (pintype "passive"))
    )
    (net (code "74") (name "Net-(R10-WIPER)") (class "Default")
      (node (ref "JP10") (pin "1") (pinfunction "1_1") (pintype "passive"))
      (node (ref "R10") (pin "2") (pinfunction "WIPER_2") (pintype "passive"))
    )
    (net (code "75") (name "Net-(R11-WIPER)") (class "Default")
      (node (ref "JP10") (pin "2") (pinfunction "2_2") (pintype "passive"))
      (node (ref "R11") (pin "2") (pinfunction "WIPER_2") (pintype "passive"))
    )
    (net (code "76") (name "Net-(R12-1)") (class "Default")
      (node (ref "R12") (pin "P$1") (pinfunction "1_P$1") (pintype "passive"))
      (node (ref "U2") (pin "15") (pinfunction "A_15") (pintype "power_in"))
    )
    (net (code "77") (name "Net-(R13-WIPER)") (class "Default")
      (node (ref "R13") (pin "2") (pinfunction "WIPER_2") (pintype "passive"))
      (node (ref "U2") (pin "3") (pinfunction "VO_3") (pintype "bidirectional"))
    )
    (net (code "78") (name "Net-(R14-2)") (class "Default")
      (node (ref "LED1") (pin "A") (pinfunction "A_A") (pintype "passive"))
      (node (ref "R14") (pin "P$2") (pinfunction "2_P$2") (pintype "passive"))
    )
    (net (code "79") (name "Net-(R19-1)") (class "Default")
      (node (ref "JP13") (pin "2") (pinfunction "2_2") (pintype "passive"))
      (node (ref "R19") (pin "P$1") (pinfunction "1_P$1") (pintype "passive"))
      (node (ref "S2") (pin "1") (pinfunction "1_1") (pintype "passive"))
    )
    (net (code "80") (name "Net-(R20-1)") (class "Default")
      (node (ref "JP13") (pin "1") (pinfunction "1_1") (pintype "passive"))
      (node (ref "R20") (pin "P$1") (pinfunction "1_P$1") (pintype "passive"))
      (node (ref "S3") (pin "1") (pinfunction "1_1") (pintype "passive"))
    )
    (net (code "81") (name "Net-(R21-2)") (class "Default")
      (node (ref "JP15") (pin "1") (pinfunction "1_1") (pintype "passive"))
      (node (ref "R21") (pin "P$2") (pinfunction "2_P$2") (pintype "passive"))
    )
    (net (code "82") (name "Net-(R22-2)") (class "Default")
      (node (ref "JP16") (pin "1") (pinfunction "1_1") (pintype "passive"))
      (node (ref "R22") (pin "P$2") (pinfunction "2_P$2") (pintype "passive"))
    )
    (net (code "83") (name "Net-(U1-RA6)") (class "Default")
      (node (ref "C2") (pin "1") (pinfunction "1_1") (pintype "passive"))
      (node (ref "U1") (pin "14") (pinfunction "RA6_14") (pintype "passive"))
      (node (ref "Y1") (pin "2") (pinfunction "2_2") (pintype "passive"))
    )
    (net (code "84") (name "Net-(U1-RA7)") (class "Default")
      (node (ref "C1") (pin "1") (pinfunction "1_1") (pintype "passive"))
      (node (ref "U1") (pin "13") (pinfunction "RA7_13") (pintype "passive"))
      (node (ref "Y1") (pin "1") (pinfunction "1_1") (pintype "passive"))
    )
    (net (code "85") (name "unconnected-(ICSP1-PGM-Pad1)") (class "Default")
      (node (ref "ICSP1") (pin "1") (pinfunction "PGM_1") (pintype "bidirectional"))
    )
    (net (code "86") (name "unconnected-(JP2-CTS-PadP$5)") (class "Default")
      (node (ref "JP2") (pin "P$5") (pinfunction "CTS_P$5") (pintype "bidirectional"))
    )
  )
)
